# DFB.net
KiCad netlist of a schematic drawn in Altium Designer
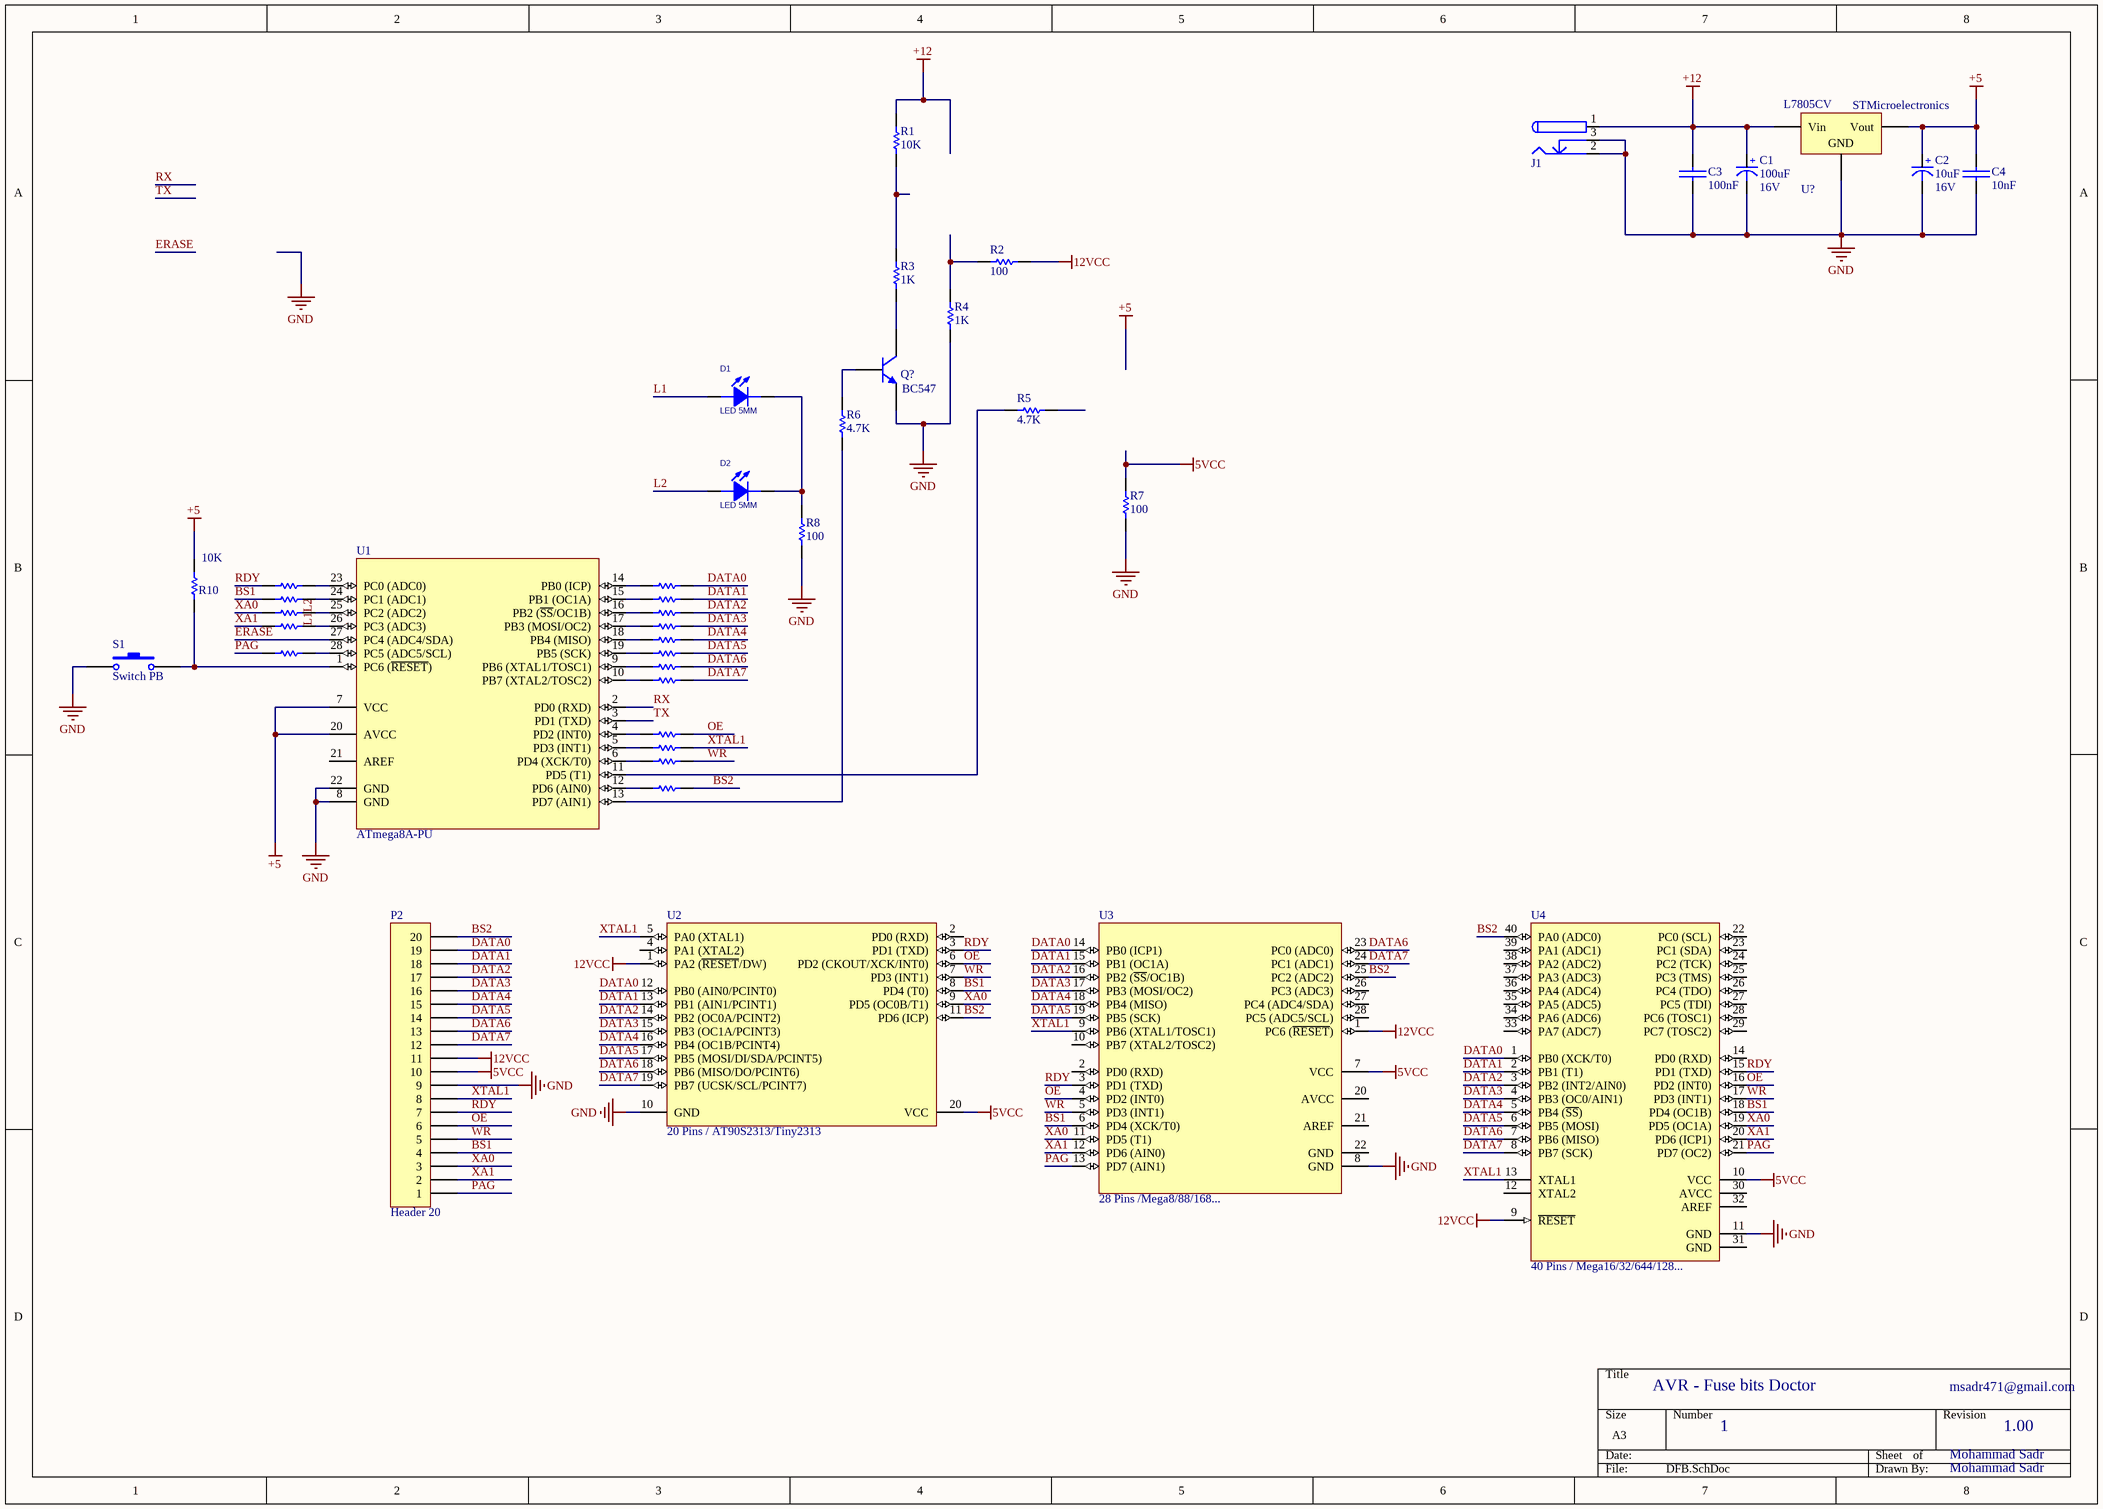
[diagram p0: DFB.SchDoc]
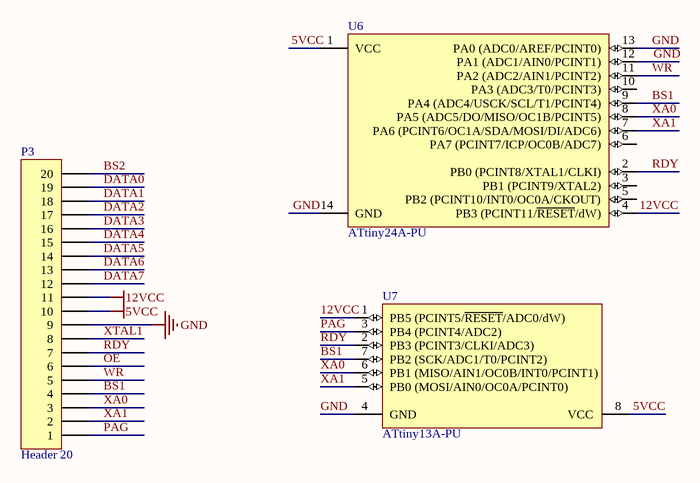
[diagram p1: DFB (ADAPTER).SchDoc]

(export (version "E")
  (design (tool "Eeschema 10.0.6"))
  (components
    (comp (ref "P3")
      (value "Header 20")
      (footprint "HDR1X20")
      (description "Header, 20-Pin")
      (fields (field (name "PUBLISHER") "Altium Limited"))
      (libsource (lib "Altium") (part "Header 20"))
    )
    (comp (ref "U6")
      (value "ATtiny24A-PU")
      (footprint "14P3")
      (fields (field (name "PUBLISHER") "Altium Limited"))
      (libsource (lib "Atmel Microcontroller 8-Bit tinyAVR") (part "ATtiny24A-PU"))
    )
    (comp (ref "U7")
      (value "ATtiny13A-PU")
      (footprint "8P3")
      (fields (field (name "PUBLISHER") "Altium Limited"))
      (libsource (lib "Atmel Microcontroller 8-Bit tinyAVR") (part "ATtiny13A-PU"))
    )
  )
  (nets
    (net (code "1") (name "/BS1") (class "Default")
      (node (ref "P3") (pin "4") (pinfunction "4_4") (pintype "passive"))
      (node (ref "U6") (pin "9") (pinfunction "PA4_(ADC4/USCK/SCL/T1/PCINT4)_9") (pintype "bidirectional"))
      (node (ref "U7") (pin "7") (pinfunction "PB2_(SCK/ADC1/T0/PCINT2)_7") (pintype "bidirectional"))
    )
    (net (code "2") (name "/BS2") (class "Default")
      (node (ref "P3") (pin "20") (pinfunction "20_20") (pintype "passive"))
    )
    (net (code "3") (name "/DATA0") (class "Default")
      (node (ref "P3") (pin "19") (pinfunction "19_19") (pintype "passive"))
    )
    (net (code "4") (name "/DATA1") (class "Default")
      (node (ref "P3") (pin "18") (pinfunction "18_18") (pintype "passive"))
    )
    (net (code "5") (name "/DATA2") (class "Default")
      (node (ref "P3") (pin "17") (pinfunction "17_17") (pintype "passive"))
    )
    (net (code "6") (name "/DATA3") (class "Default")
      (node (ref "P3") (pin "16") (pinfunction "16_16") (pintype "passive"))
    )
    (net (code "7") (name "/DATA4") (class "Default")
      (node (ref "P3") (pin "15") (pinfunction "15_15") (pintype "passive"))
    )
    (net (code "8") (name "/DATA5") (class "Default")
      (node (ref "P3") (pin "14") (pinfunction "14_14") (pintype "passive"))
    )
    (net (code "9") (name "/DATA6") (class "Default")
      (node (ref "P3") (pin "13") (pinfunction "13_13") (pintype "passive"))
    )
    (net (code "10") (name "/DATA7") (class "Default")
      (node (ref "P3") (pin "12") (pinfunction "12_12") (pintype "passive"))
    )
    (net (code "11") (name "/OE") (class "Default")
      (node (ref "P3") (pin "6") (pinfunction "6_6") (pintype "passive"))
    )
    (net (code "12") (name "/PAG") (class "Default")
      (node (ref "P3") (pin "1") (pinfunction "1_1") (pintype "passive"))
      (node (ref "U7") (pin "3") (pinfunction "PB4_(PCINT4/ADC2)_3") (pintype "bidirectional"))
    )
    (net (code "13") (name "/RDY") (class "Default")
      (node (ref "P3") (pin "7") (pinfunction "7_7") (pintype "passive"))
      (node (ref "U6") (pin "2") (pinfunction "PB0_(PCINT8/XTAL1/CLKI)_2") (pintype "bidirectional"))
      (node (ref "U7") (pin "2") (pinfunction "PB3_(PCINT3/CLKI/ADC3)_2") (pintype "bidirectional"))
    )
    (net (code "14") (name "/WR") (class "Default")
      (node (ref "P3") (pin "5") (pinfunction "5_5") (pintype "passive"))
      (node (ref "U6") (pin "11") (pinfunction "PA2_(ADC2/AIN1/PCINT2)_11") (pintype "bidirectional"))
    )
    (net (code "15") (name "/XA0") (class "Default")
      (node (ref "P3") (pin "3") (pinfunction "3_3") (pintype "passive"))
      (node (ref "U6") (pin "8") (pinfunction "PA5_(ADC5/DO/MISO/OC1B/PCINT5)_8") (pintype "bidirectional"))
      (node (ref "U7") (pin "6") (pinfunction "PB1_(MISO/AIN1/OC0B/INT0/PCINT1)_6") (pintype "bidirectional"))
    )
    (net (code "16") (name "/XA1") (class "Default")
      (node (ref "P3") (pin "2") (pinfunction "2_2") (pintype "passive"))
      (node (ref "U6") (pin "7") (pinfunction "PA6_(PCINT6/OC1A/SDA/MOSI/DI/ADC6)_7") (pintype "bidirectional"))
      (node (ref "U7") (pin "5") (pinfunction "PB0_(MOSI/AIN0/OC0A/PCINT0)_5") (pintype "bidirectional"))
    )
    (net (code "17") (name "/XTAL1") (class "Default")
      (node (ref "P3") (pin "8") (pinfunction "8_8") (pintype "passive"))
    )
    (net (code "18") (name "5VCC") (class "Default")
      (node (ref "P3") (pin "10") (pinfunction "10_10") (pintype "passive"))
      (node (ref "U6") (pin "1") (pinfunction "VCC_1") (pintype "power_in"))
      (node (ref "U7") (pin "8") (pinfunction "VCC_8") (pintype "power_in"))
    )
    (net (code "19") (name "12VCC") (class "Default")
      (node (ref "P3") (pin "11") (pinfunction "11_11") (pintype "passive"))
      (node (ref "U6") (pin "4") (pinfunction "PB3_(PCINT11/~{RESET}/dW)_4") (pintype "bidirectional"))
      (node (ref "U7") (pin "1") (pinfunction "PB5_(PCINT5/~{RESET}/ADC0/dW)_1") (pintype "bidirectional"))
    )
    (net (code "20") (name "GND") (class "Default")
      (node (ref "P3") (pin "9") (pinfunction "9_9") (pintype "passive"))
      (node (ref "U6") (pin "12") (pinfunction "PA1_(ADC1/AIN0/PCINT1)_12") (pintype "bidirectional"))
      (node (ref "U6") (pin "13") (pinfunction "PA0_(ADC0/AREF/PCINT0)_13") (pintype "bidirectional"))
      (node (ref "U6") (pin "14") (pinfunction "GND_14") (pintype "power_in"))
      (node (ref "U7") (pin "4") (pinfunction "GND_4") (pintype "power_in"))
    )
    (net (code "21") (name "unconnected-(U6-PA3_(ADC3{slash}T0{slash}PCINT3)-Pad10)") (class "Default")
      (node (ref "U6") (pin "10") (pinfunction "PA3_(ADC3/T0/PCINT3)_10") (pintype "bidirectional"))
    )
    (net (code "22") (name "unconnected-(U6-PA7_(PCINT7{slash}ICP{slash}OC0B{slash}ADC7)-Pad6)") (class "Default")
      (node (ref "U6") (pin "6") (pinfunction "PA7_(PCINT7/ICP/OC0B/ADC7)_6") (pintype "bidirectional"))
    )
    (net (code "23") (name "unconnected-(U6-PB1_(PCINT9{slash}XTAL2)-Pad3)") (class "Default")
      (node (ref "U6") (pin "3") (pinfunction "PB1_(PCINT9/XTAL2)_3") (pintype "bidirectional"))
    )
    (net (code "24") (name "unconnected-(U6-PB2_(PCINT10{slash}INT0{slash}OC0A{slash}CKOUT)-Pad5)") (class "Default")
      (node (ref "U6") (pin "5") (pinfunction "PB2_(PCINT10/INT0/OC0A/CKOUT)_5") (pintype "bidirectional"))
    )
  )
)
